# uc4h_airspeed_v0401_addonrscspi1.net
KiCad netlist of a schematic drawn in EAGLE
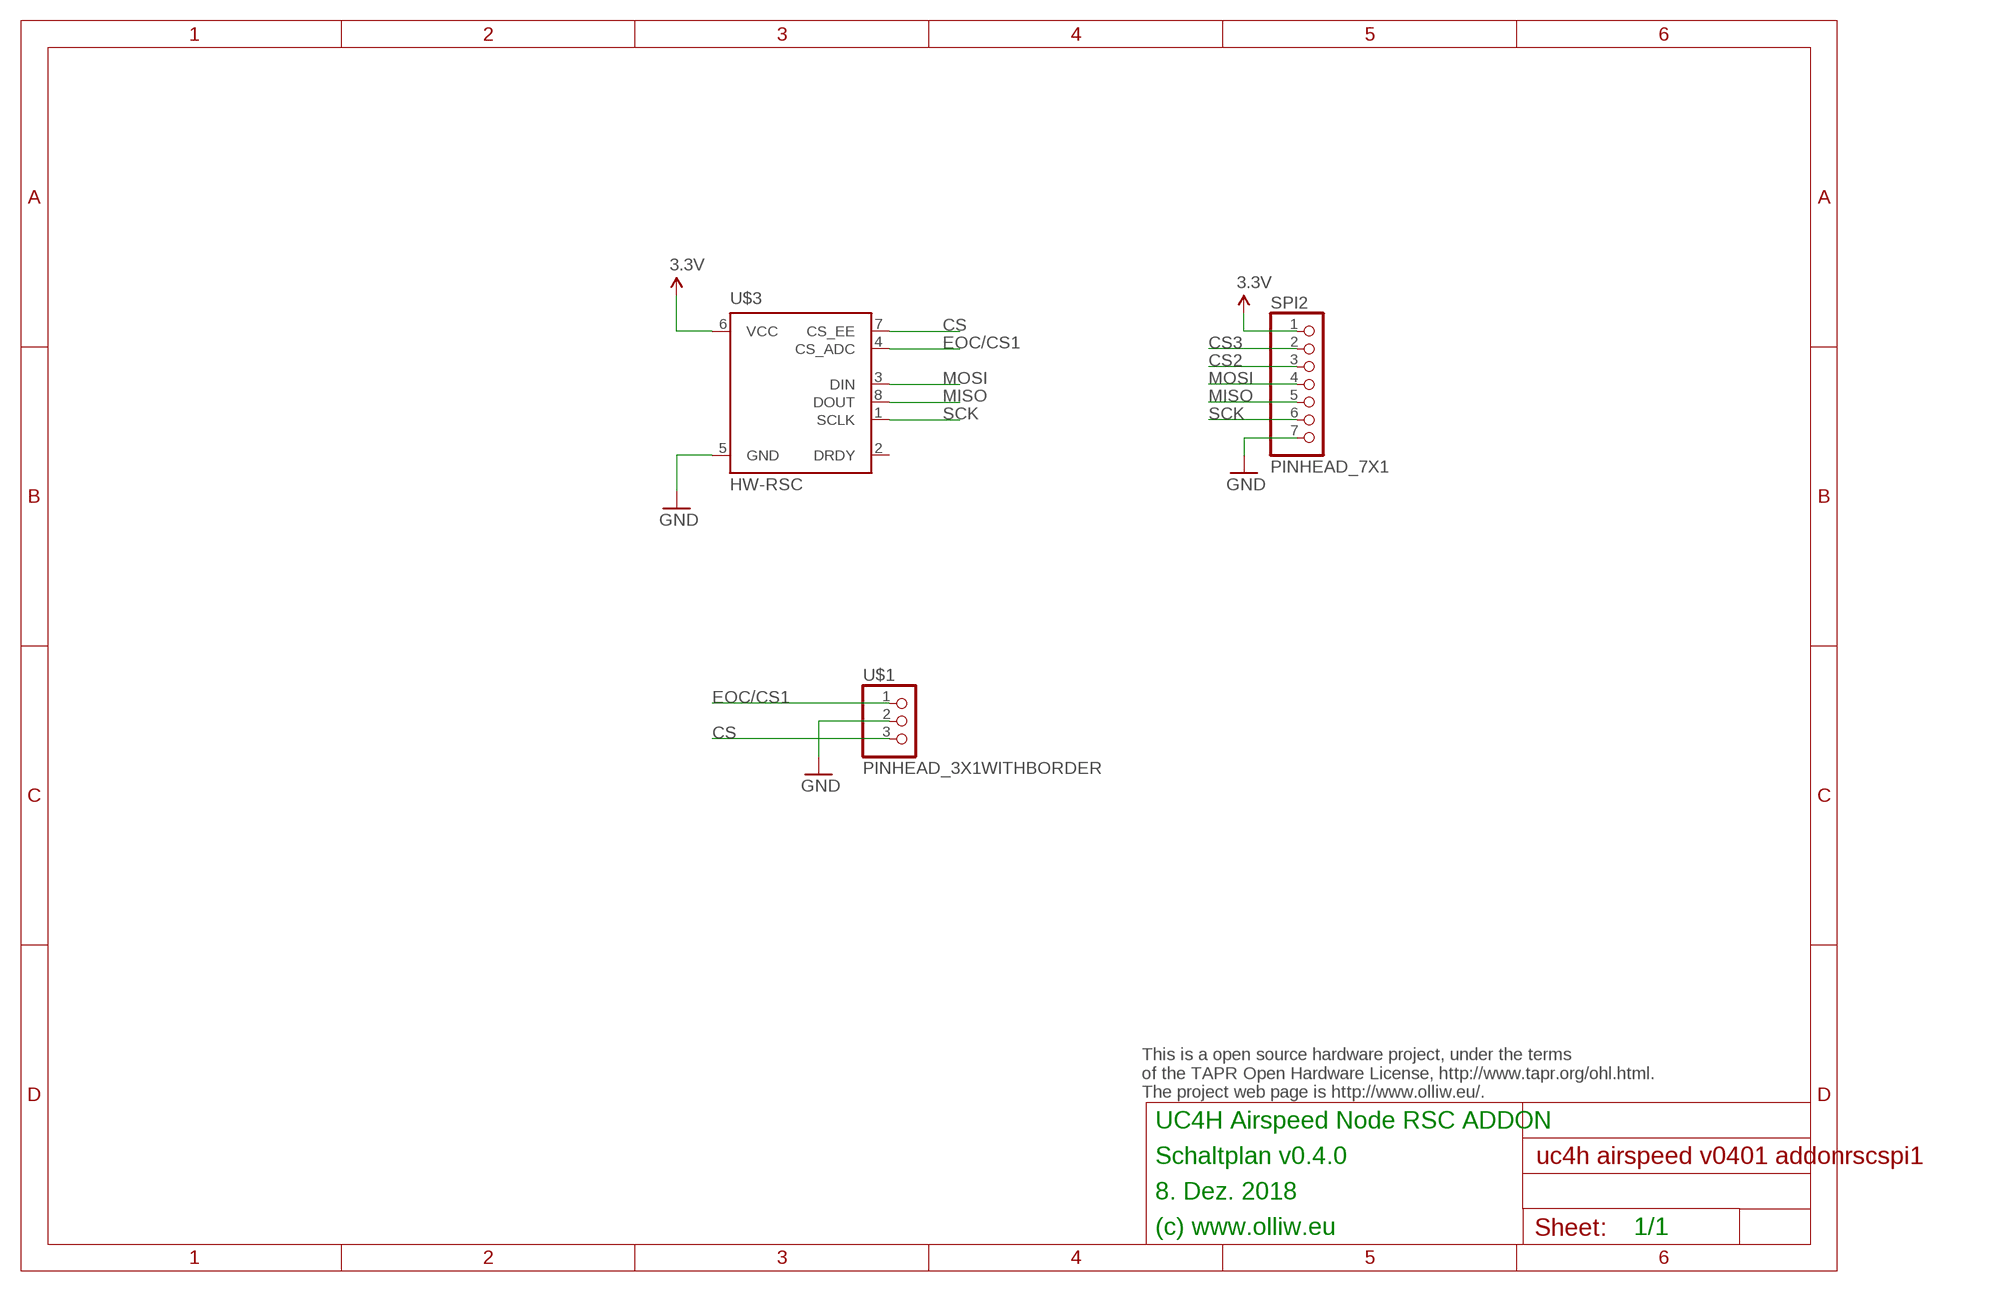
[diagram p0: schematic, sheet 1]

(export (version "E")
  (design (tool "Eeschema 10.0.6"))
  (components
    (comp (ref "SPI2")
      (value "PINHEAD_7X1")
      (footprint "eagle-import:PINHEAD_7X1")
      (libsource (lib "eagle-import") (part "PINHEAD_7X1"))
    )
    (comp (ref "U$1")
      (value "PINHEAD_3X1WITHBORDER")
      (footprint "eagle-import:PINHEAD_3X1")
      (libsource (lib "eagle-import") (part "PINHEAD_3X1WITHBORDER"))
    )
    (comp (ref "U$3")
      (value "HW-RSC")
      (footprint "eagle-import:HONEYWELL-8")
      (libsource (lib "eagle-import") (part "HW-RSC"))
    )
  )
  (nets
    (net (code "1") (name "/CS") (class "Default")
      (node (ref "U$1") (pin "3") (pinfunction "5_3") (pintype "passive"))
      (node (ref "U$3") (pin "7") (pinfunction "CS_EE_7") (pintype "input"))
    )
    (net (code "2") (name "/CS2") (class "Default")
      (node (ref "SPI2") (pin "3") (pinfunction "3_3") (pintype "passive"))
    )
    (net (code "3") (name "/CS3") (class "Default")
      (node (ref "SPI2") (pin "2") (pinfunction "2_2") (pintype "passive"))
    )
    (net (code "4") (name "/EOC{slash}CS1") (class "Default")
      (node (ref "U$1") (pin "1") (pinfunction "1_1") (pintype "passive"))
      (node (ref "U$3") (pin "4") (pinfunction "CS_ADC_4") (pintype "input"))
    )
    (net (code "5") (name "/MISO") (class "Default")
      (node (ref "SPI2") (pin "5") (pinfunction "5_5") (pintype "passive"))
      (node (ref "U$3") (pin "8") (pinfunction "DOUT_8") (pintype "output"))
    )
    (net (code "6") (name "/MOSI") (class "Default")
      (node (ref "SPI2") (pin "4") (pinfunction "4_4") (pintype "passive"))
      (node (ref "U$3") (pin "3") (pinfunction "DIN_3") (pintype "input"))
    )
    (net (code "7") (name "/SCK") (class "Default")
      (node (ref "SPI2") (pin "6") (pinfunction "6_6") (pintype "passive"))
      (node (ref "U$3") (pin "1") (pinfunction "SCLK_1") (pintype "input"))
    )
    (net (code "8") (name "3.3V") (class "Default")
      (node (ref "SPI2") (pin "1") (pinfunction "1_1") (pintype "passive"))
      (node (ref "U$3") (pin "6") (pinfunction "VCC_6") (pintype "power_in"))
    )
    (net (code "9") (name "GND") (class "Default")
      (node (ref "SPI2") (pin "7") (pinfunction "7_7") (pintype "passive"))
      (node (ref "U$1") (pin "2") (pinfunction "3_2") (pintype "passive"))
      (node (ref "U$3") (pin "5") (pinfunction "GND_5") (pintype "power_in"))
    )
    (net (code "10") (name "unconnected-(U$3-DRDY-Pad2)") (class "Default")
      (node (ref "U$3") (pin "2") (pinfunction "DRDY_2") (pintype "output"))
    )
  )
)
